# TensoSensor_EXTRA.net
KiCad netlist of a schematic drawn in Altium Designer
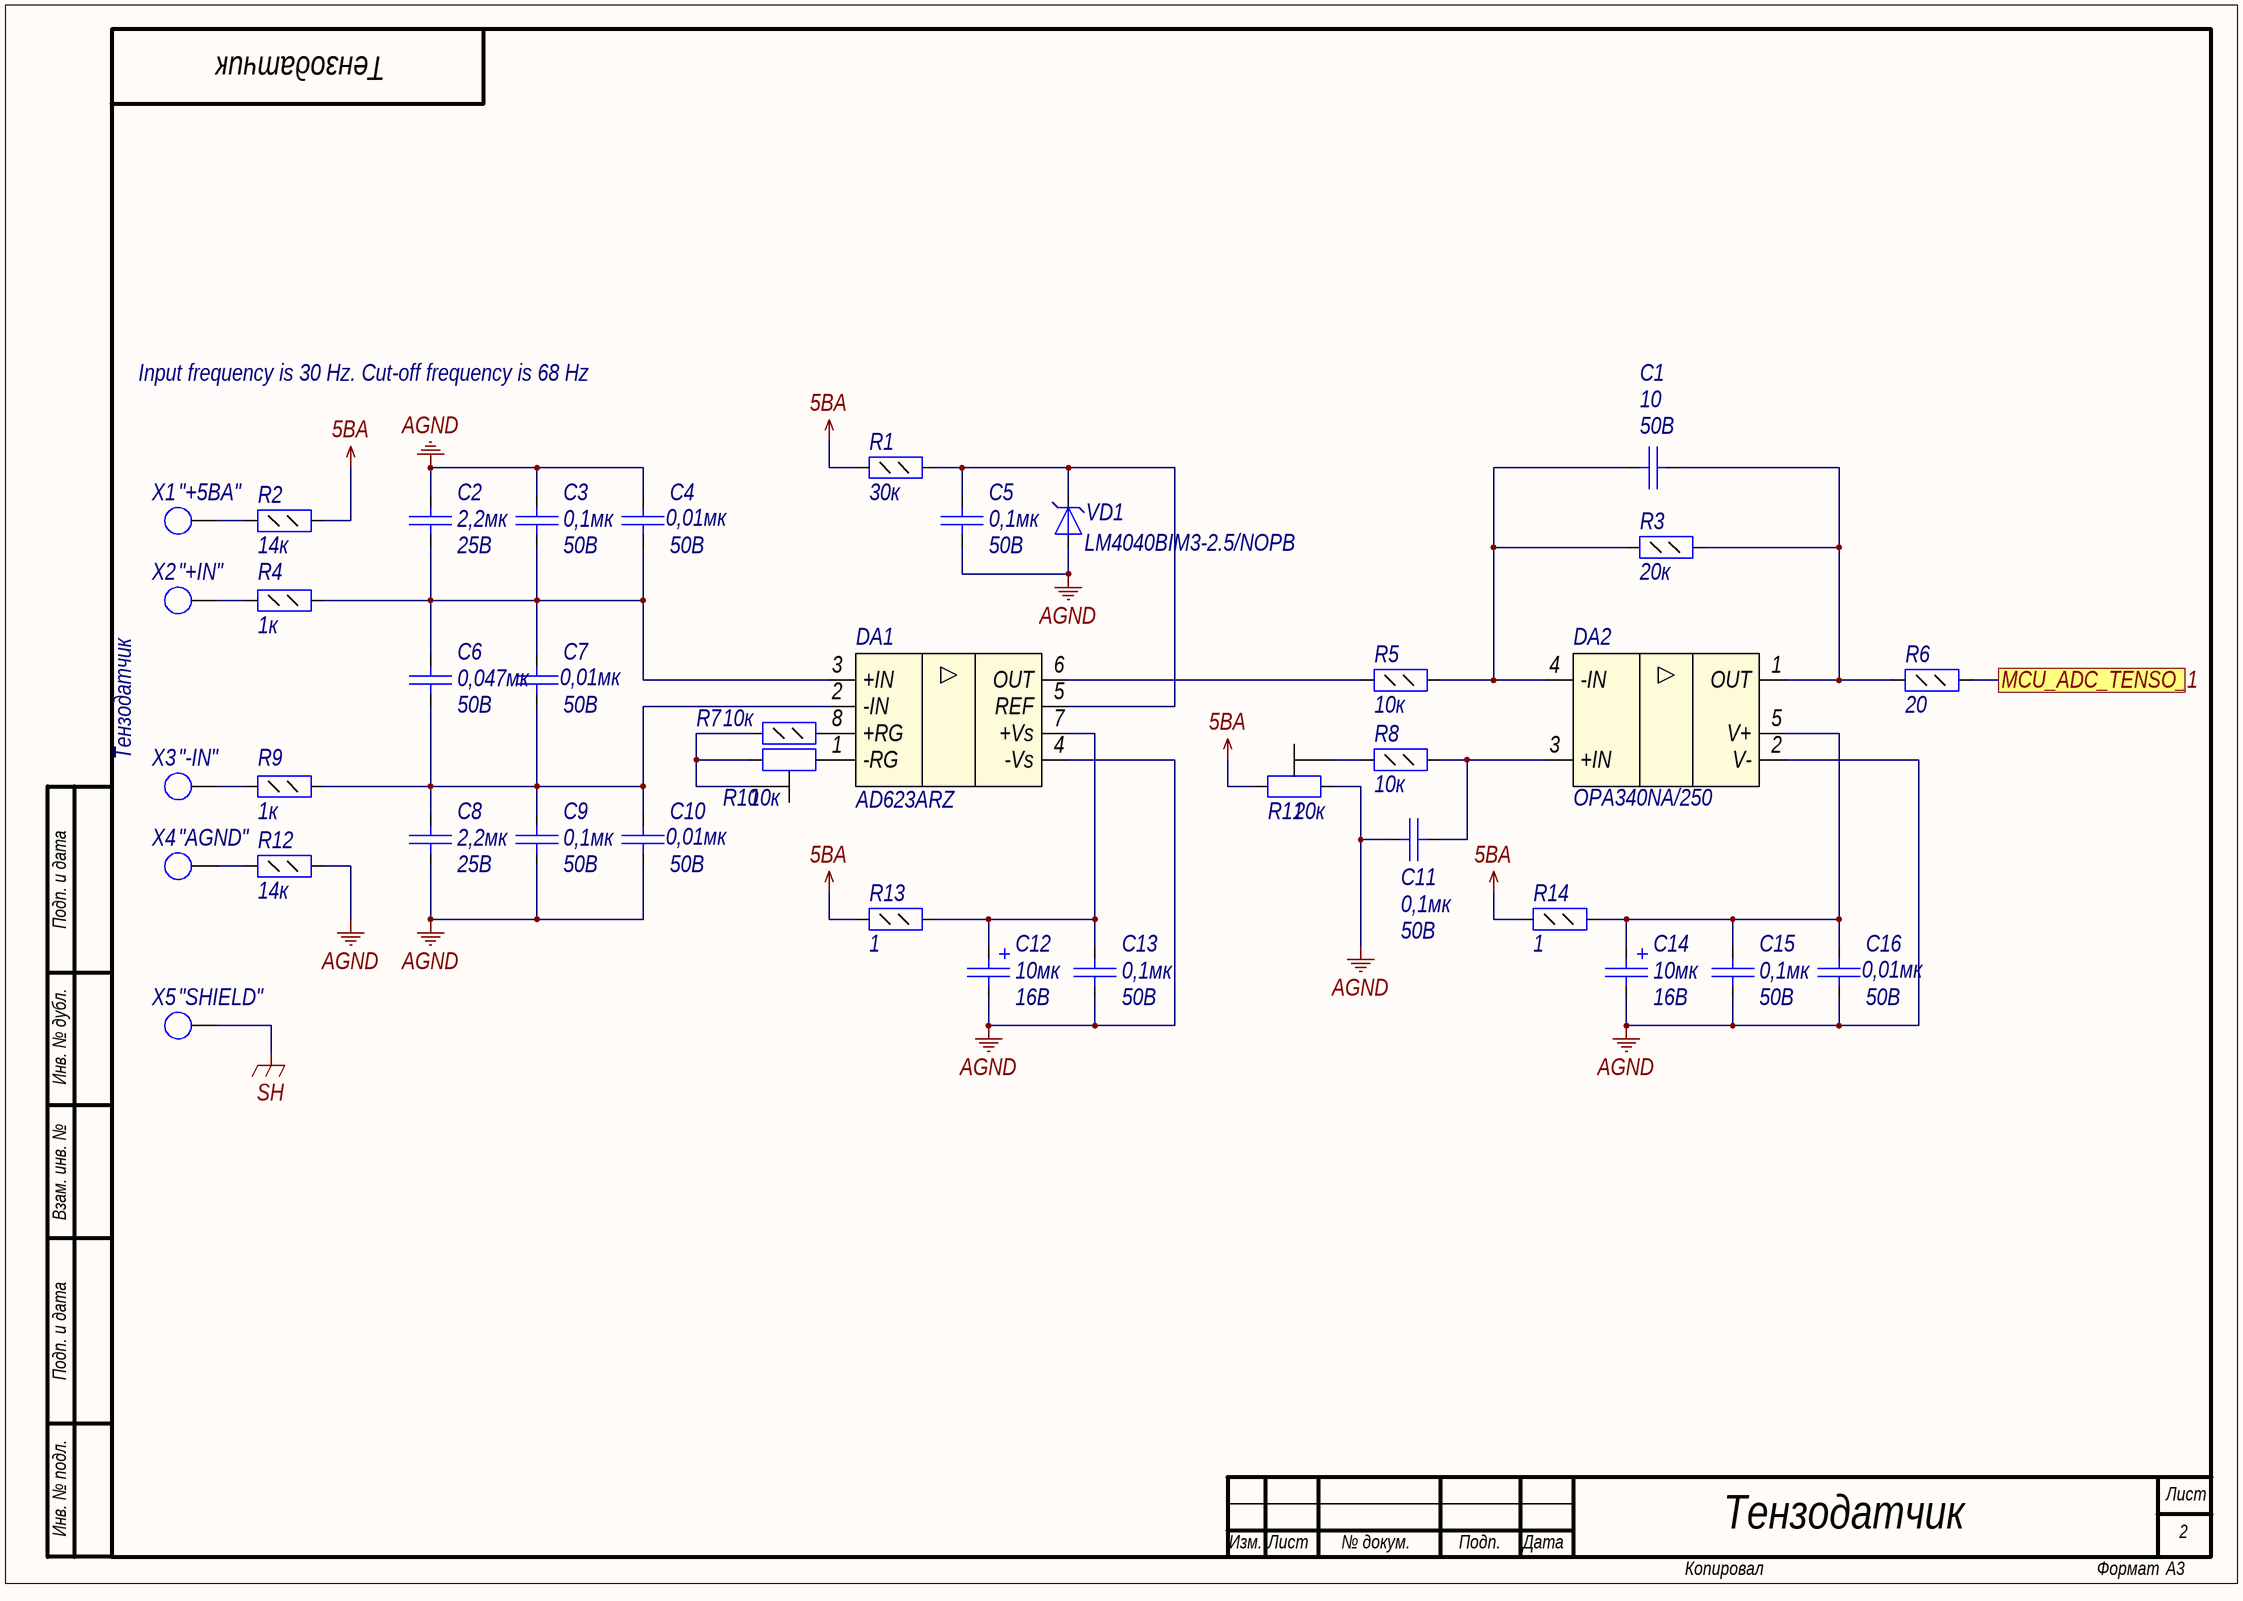
[diagram p0: TensoSensor_EXTRA.SchDoc]

(export (version "E")
  (design (tool "Eeschema 10.0.6"))
  (components
    (comp (ref "C1")
      (value "10")
      (footprint "C0603")
      (description "Конденсатор")
      (fields (field (name "VOLTAGE") "50B") (field (name "PART NUMBER") "GRM1885C1H100J"))
      (libsource (lib "MOP44") (part "Capacitor"))
    )
    (comp (ref "C2")
      (value "2,2мк")
      (footprint "C0805")
      (description "Конденсатор")
      (fields (field (name "VOLTAGE") "25B") (field (name "PART NUMBER") "GRM21BR71E225K"))
      (libsource (lib "MOP44") (part "Capacitor"))
    )
    (comp (ref "C3")
      (value "0,1мк")
      (footprint "C0805")
      (description "Конденсатор")
      (fields (field (name "VOLTAGE") "50B") (field (name "PART NUMBER") "GRM21BR71H104K**"))
      (libsource (lib "MOP44") (part "Capacitor"))
    )
    (comp (ref "C4")
      (value "0,01мк")
      (footprint "C0805")
      (description "Конденсатор")
      (fields (field (name "VOLTAGE") "50B") (field (name "PART NUMBER") "GRM216R71H103K"))
      (libsource (lib "MOP44") (part "Capacitor"))
    )
    (comp (ref "C5")
      (value "0,1мк")
      (footprint "C0805")
      (description "Конденсатор")
      (fields (field (name "VOLTAGE") "50B") (field (name "PART NUMBER") "GRM21BR71H104K**"))
      (libsource (lib "MOP44") (part "Capacitor"))
    )
    (comp (ref "C6")
      (value "0,047мк")
      (footprint "C0805")
      (description "Конденсатор")
      (fields (field (name "VOLTAGE") "50B") (field (name "PART NUMBER") "GRM21BR71H473K"))
      (libsource (lib "MOP44") (part "Capacitor"))
    )
    (comp (ref "C7")
      (value "0,01мк")
      (footprint "C0805")
      (description "Конденсатор")
      (fields (field (name "VOLTAGE") "50B") (field (name "PART NUMBER") "GRM216R71H103K"))
      (libsource (lib "MOP44") (part "Capacitor"))
    )
    (comp (ref "C8")
      (value "2,2мк")
      (footprint "C0805")
      (description "Конденсатор")
      (fields (field (name "VOLTAGE") "25B") (field (name "PART NUMBER") "GRM21BR71E225K"))
      (libsource (lib "MOP44") (part "Capacitor"))
    )
    (comp (ref "C9")
      (value "0,1мк")
      (footprint "C0805")
      (description "Конденсатор")
      (fields (field (name "VOLTAGE") "50B") (field (name "PART NUMBER") "GRM21BR71H104K**"))
      (libsource (lib "MOP44") (part "Capacitor"))
    )
    (comp (ref "C10")
      (value "0,01мк")
      (footprint "C0805")
      (description "Конденсатор")
      (fields (field (name "VOLTAGE") "50B") (field (name "PART NUMBER") "GRM216R71H103K"))
      (libsource (lib "MOP44") (part "Capacitor"))
    )
    (comp (ref "C11")
      (value "0,1мк")
      (footprint "C0805")
      (description "Конденсатор")
      (fields (field (name "VOLTAGE") "50B") (field (name "PART NUMBER") "GRM21BR71H104K**"))
      (libsource (lib "MOP44") (part "Capacitor"))
    )
    (comp (ref "C12")
      (value "10мк")
      (footprint "TANTAL CASE A")
      (description "Конденсатор полярный")
      (fields
        (field (name "VOLTAGE") "16В")
        (field (name "PART NUMBER") "293D106X9016A2TE3")
        (field (name "Comment") "Capacitor_pol")
      )
      (libsource (lib "MOP44") (part "Capacitor_pol"))
    )
    (comp (ref "C13")
      (value "0,1мк")
      (footprint "C0805")
      (description "Конденсатор")
      (fields (field (name "VOLTAGE") "50B") (field (name "PART NUMBER") "GRM21BR71H104K**"))
      (libsource (lib "MOP44") (part "Capacitor"))
    )
    (comp (ref "C14")
      (value "10мк")
      (footprint "TANTAL CASE A")
      (description "Конденсатор полярный")
      (fields
        (field (name "VOLTAGE") "16В")
        (field (name "PART NUMBER") "293D106X9016A2TE3")
        (field (name "Comment") "Capacitor_pol")
      )
      (libsource (lib "MOP44") (part "Capacitor_pol"))
    )
    (comp (ref "C15")
      (value "0,1мк")
      (footprint "C0805")
      (description "Конденсатор")
      (fields (field (name "VOLTAGE") "50B") (field (name "PART NUMBER") "GRM21BR71H104K**"))
      (libsource (lib "MOP44") (part "Capacitor"))
    )
    (comp (ref "C16")
      (value "0,01мк")
      (footprint "C0805")
      (description "Конденсатор")
      (fields (field (name "VOLTAGE") "50B") (field (name "PART NUMBER") "GRM216R71H103K"))
      (libsource (lib "MOP44") (part "Capacitor"))
    )
    (comp (ref "DA1")
      (value "AD623ARZ")
      (footprint "SO8")
      (description "Low Cost Low Power  Instrumentation Amplifier")
      (libsource (lib "MOP44") (part "AD623ARZ"))
    )
    (comp (ref "DA2")
      (value "OPA340")
      (footprint "SOT23-5")
      (description "Operational Amplifiers\r\nMicroAmplifier")
      (fields (field (name "PART NUMBER") "OPA340NA/250"))
      (libsource (lib "MOP44") (part "OPA340"))
    )
    (comp (ref "R1")
      (value "30к")
      (footprint "R0805")
      (description "Резистор")
      (fields (field (name "PART NUMBER") "RC0805FR-0730KL") (field (name "POWER") "0,125Вт"))
      (libsource (lib "MOP44") (part "Resistor_0,125Вт"))
    )
    (comp (ref "R2")
      (value "14к")
      (footprint "R0805")
      (description "Резистор")
      (fields (field (name "PART NUMBER") "RC0805FR-0714KL") (field (name "POWER") "0,125Вт"))
      (libsource (lib "MOP44") (part "Resistor_0,125Вт"))
    )
    (comp (ref "R3")
      (value "20к")
      (footprint "R0805")
      (description "Резистор")
      (fields (field (name "PART NUMBER") "RC0805FR-0720KL") (field (name "POWER") "0,125Вт"))
      (libsource (lib "MOP44") (part "Resistor_0,125Вт"))
    )
    (comp (ref "R4")
      (value "1к")
      (footprint "R0805")
      (description "Резистор")
      (fields (field (name "PART NUMBER") "RC0805FR-071KL") (field (name "POWER") "0,125Вт"))
      (libsource (lib "MOP44") (part "Resistor_0,125Вт"))
    )
    (comp (ref "R5")
      (value "10к")
      (footprint "R0805")
      (description "Резистор")
      (fields (field (name "PART NUMBER") "RC0805FR-0710KL") (field (name "POWER") "0,125Вт"))
      (libsource (lib "MOP44") (part "Resistor_0,125Вт"))
    )
    (comp (ref "R6")
      (value "20")
      (footprint "R0805")
      (description "Резистор")
      (fields (field (name "PART NUMBER") "RC0805FR-0720RL") (field (name "POWER") "0,125Вт"))
      (libsource (lib "MOP44") (part "Resistor_0,125Вт"))
    )
    (comp (ref "R7")
      (value "10к")
      (footprint "R0805")
      (description "Резистор")
      (fields (field (name "PART NUMBER") "RC0805FR-0710KL") (field (name "POWER") "0,125Вт"))
      (libsource (lib "MOP44") (part "Resistor_0,125Вт"))
    )
    (comp (ref "R8")
      (value "10к")
      (footprint "R0805")
      (description "Резистор")
      (fields (field (name "PART NUMBER") "RC0805FR-0710KL") (field (name "POWER") "0,125Вт"))
      (libsource (lib "MOP44") (part "Resistor_0,125Вт"))
    )
    (comp (ref "R9")
      (value "1к")
      (footprint "R0805")
      (description "Резистор")
      (fields (field (name "PART NUMBER") "RC0805FR-071KL") (field (name "POWER") "0,125Вт"))
      (libsource (lib "MOP44") (part "Resistor_0,125Вт"))
    )
    (comp (ref "R10")
      (value "10к")
      (footprint "3224W")
      (description "Potentiometer")
      (fields (field (name "PART NUMBER") "3224W-1-103E") (field (name "POWER") "0,25Вт"))
      (libsource (lib "MOP44") (part "Potentiometer"))
    )
    (comp (ref "R11")
      (value "20к")
      (footprint "3224W")
      (description "Potentiometer")
      (fields (field (name "PART NUMBER") "3224W-1-203E") (field (name "POWER") "0,25Вт"))
      (libsource (lib "") (part "Potentiometer_1"))
    )
    (comp (ref "R12")
      (value "14к")
      (footprint "R0805")
      (description "Резистор")
      (fields (field (name "PART NUMBER") "RC0805FR-0714KL") (field (name "POWER") "0,125Вт"))
      (libsource (lib "MOP44") (part "Resistor_0,125Вт"))
    )
    (comp (ref "R13")
      (value "1")
      (footprint "R0805")
      (description "Резистор")
      (fields (field (name "PART NUMBER") "RC0805FR-071RL") (field (name "POWER") "0,125Вт"))
      (libsource (lib "MOP44") (part "Resistor_0,125Вт"))
    )
    (comp (ref "R14")
      (value "1")
      (footprint "R0805")
      (description "Резистор")
      (fields (field (name "PART NUMBER") "RC0805FR-071RL") (field (name "POWER") "0,125Вт"))
      (libsource (lib "MOP44") (part "Resistor_0,125Вт"))
    )
    (comp (ref "VD1")
      (value "LM4040BIM3-2.5/NOPB")
      (footprint "SOT23-3")
      (description "Прецезионный источник опорного напряжения")
      (libsource (lib "MOP44") (part "LM4040BIM3-2.5/NOPB"))
    )
    (comp (ref "X1") (value "SoldPoint") (footprint "1HOLE") (libsource (lib "MOP44") (part "SoldPoint")))
    (comp (ref "X2") (value "SoldPoint") (footprint "1HOLE") (libsource (lib "MOP44") (part "SoldPoint")))
    (comp (ref "X3") (value "SoldPoint") (footprint "1HOLE") (libsource (lib "MOP44") (part "SoldPoint")))
    (comp (ref "X4") (value "SoldPoint") (footprint "1HOLE") (libsource (lib "MOP44") (part "SoldPoint")))
    (comp (ref "X5") (value "SoldPoint") (footprint "1HOLE") (libsource (lib "MOP44") (part "SoldPoint")))
  )
  (nets
    (net (code "1") (name "/MCU_ADC_TENSO_1") (class "Default")
      (node (ref "R6") (pin "2") (pinfunction "2_2") (pintype "passive"))
    )
    (net (code "2") (name "5BA") (class "Default")
      (node (ref "R1") (pin "1") (pinfunction "1_1") (pintype "passive"))
      (node (ref "R11") (pin "1") (pinfunction "1_1") (pintype "passive"))
      (node (ref "R13") (pin "1") (pinfunction "1_1") (pintype "passive"))
      (node (ref "R14") (pin "1") (pinfunction "1_1") (pintype "passive"))
      (node (ref "R2") (pin "2") (pinfunction "2_2") (pintype "passive"))
    )
    (net (code "3") (name "AGND") (class "Default")
      (node (ref "C10") (pin "1") (pinfunction "1_1") (pintype "passive"))
      (node (ref "C11") (pin "2") (pinfunction "2_2") (pintype "passive"))
      (node (ref "C12") (pin "2") (pinfunction "2_2") (pintype "passive"))
      (node (ref "C13") (pin "1") (pinfunction "1_1") (pintype "passive"))
      (node (ref "C14") (pin "2") (pinfunction "2_2") (pintype "passive"))
      (node (ref "C15") (pin "1") (pinfunction "1_1") (pintype "passive"))
      (node (ref "C16") (pin "1") (pinfunction "1_1") (pintype "passive"))
      (node (ref "C2") (pin "2") (pinfunction "2_2") (pintype "passive"))
      (node (ref "C3") (pin "2") (pinfunction "2_2") (pintype "passive"))
      (node (ref "C4") (pin "2") (pinfunction "2_2") (pintype "passive"))
      (node (ref "C5") (pin "1") (pinfunction "1_1") (pintype "passive"))
      (node (ref "C8") (pin "1") (pinfunction "1_1") (pintype "passive"))
      (node (ref "C9") (pin "1") (pinfunction "1_1") (pintype "passive"))
      (node (ref "DA1") (pin "4") (pinfunction "-Vs_4") (pintype "passive"))
      (node (ref "DA2") (pin "2") (pinfunction "V-_2") (pintype "passive"))
      (node (ref "R11") (pin "3") (pinfunction "3_3") (pintype "passive"))
      (node (ref "R12") (pin "2") (pinfunction "2_2") (pintype "passive"))
      (node (ref "VD1") (pin "2") (pinfunction "A_2") (pintype "passive"))
    )
    (net (code "4") (name "Net-(DA1-+IN)") (class "Default")
      (node (ref "C2") (pin "1") (pinfunction "1_1") (pintype "passive"))
      (node (ref "C3") (pin "1") (pinfunction "1_1") (pintype "passive"))
      (node (ref "C4") (pin "1") (pinfunction "1_1") (pintype "passive"))
      (node (ref "C6") (pin "2") (pinfunction "2_2") (pintype "passive"))
      (node (ref "C7") (pin "2") (pinfunction "2_2") (pintype "passive"))
      (node (ref "DA1") (pin "3") (pinfunction "+IN_3") (pintype "passive"))
      (node (ref "R4") (pin "2") (pinfunction "2_2") (pintype "passive"))
    )
    (net (code "5") (name "Net-(DA1-+RG)") (class "Default")
      (node (ref "DA1") (pin "8") (pinfunction "+RG_8") (pintype "passive"))
      (node (ref "R7") (pin "2") (pinfunction "2_2") (pintype "passive"))
    )
    (net (code "6") (name "Net-(DA1-+Vs)") (class "Default")
      (node (ref "C12") (pin "1") (pinfunction "1_1") (pintype "passive"))
      (node (ref "C13") (pin "2") (pinfunction "2_2") (pintype "passive"))
      (node (ref "DA1") (pin "7") (pinfunction "+Vs_7") (pintype "passive"))
      (node (ref "R13") (pin "2") (pinfunction "2_2") (pintype "passive"))
    )
    (net (code "7") (name "Net-(DA1--IN)") (class "Default")
      (node (ref "C10") (pin "2") (pinfunction "2_2") (pintype "passive"))
      (node (ref "C6") (pin "1") (pinfunction "1_1") (pintype "passive"))
      (node (ref "C7") (pin "1") (pinfunction "1_1") (pintype "passive"))
      (node (ref "C8") (pin "2") (pinfunction "2_2") (pintype "passive"))
      (node (ref "C9") (pin "2") (pinfunction "2_2") (pintype "passive"))
      (node (ref "DA1") (pin "2") (pinfunction "-IN_2") (pintype "passive"))
      (node (ref "R9") (pin "2") (pinfunction "2_2") (pintype "passive"))
    )
    (net (code "8") (name "Net-(DA1--RG)") (class "Default")
      (node (ref "DA1") (pin "1") (pinfunction "-RG_1") (pintype "passive"))
      (node (ref "R10") (pin "1") (pinfunction "1_1") (pintype "passive"))
    )
    (net (code "9") (name "Net-(DA1-OUT)") (class "Default")
      (node (ref "DA1") (pin "6") (pinfunction "OUT_6") (pintype "passive"))
      (node (ref "R5") (pin "1") (pinfunction "1_1") (pintype "passive"))
    )
    (net (code "10") (name "Net-(DA1-REF)") (class "Default")
      (node (ref "C5") (pin "2") (pinfunction "2_2") (pintype "passive"))
      (node (ref "DA1") (pin "5") (pinfunction "REF_5") (pintype "passive"))
      (node (ref "R1") (pin "2") (pinfunction "2_2") (pintype "passive"))
      (node (ref "VD1") (pin "1") (pinfunction "K_1") (pintype "passive"))
    )
    (net (code "11") (name "Net-(DA2-+IN)") (class "Default")
      (node (ref "C11") (pin "1") (pinfunction "1_1") (pintype "passive"))
      (node (ref "DA2") (pin "3") (pinfunction "+IN_3") (pintype "passive"))
      (node (ref "R8") (pin "2") (pinfunction "2_2") (pintype "passive"))
    )
    (net (code "12") (name "Net-(DA2--IN)") (class "Default")
      (node (ref "C1") (pin "1") (pinfunction "1_1") (pintype "passive"))
      (node (ref "DA2") (pin "4") (pinfunction "-IN_4") (pintype "passive"))
      (node (ref "R3") (pin "1") (pinfunction "1_1") (pintype "passive"))
      (node (ref "R5") (pin "2") (pinfunction "2_2") (pintype "passive"))
    )
    (net (code "13") (name "Net-(DA2-OUT)") (class "Default")
      (node (ref "C1") (pin "2") (pinfunction "2_2") (pintype "passive"))
      (node (ref "DA2") (pin "1") (pinfunction "OUT_1") (pintype "passive"))
      (node (ref "R3") (pin "2") (pinfunction "2_2") (pintype "passive"))
      (node (ref "R6") (pin "1") (pinfunction "1_1") (pintype "passive"))
    )
    (net (code "14") (name "Net-(DA2-V+)") (class "Default")
      (node (ref "C14") (pin "1") (pinfunction "1_1") (pintype "passive"))
      (node (ref "C15") (pin "2") (pinfunction "2_2") (pintype "passive"))
      (node (ref "C16") (pin "2") (pinfunction "2_2") (pintype "passive"))
      (node (ref "DA2") (pin "5") (pinfunction "V+_5") (pintype "passive"))
      (node (ref "R14") (pin "2") (pinfunction "2_2") (pintype "passive"))
    )
    (net (code "15") (name "Net-(R2-Pad1)") (class "Default")
      (node (ref "R2") (pin "1") (pinfunction "1_1") (pintype "passive"))
      (node (ref "X1") (pin "1") (pinfunction "1_1") (pintype "passive"))
    )
    (net (code "16") (name "Net-(R4-Pad1)") (class "Default")
      (node (ref "R4") (pin "1") (pinfunction "1_1") (pintype "passive"))
      (node (ref "X2") (pin "1") (pinfunction "1_1") (pintype "passive"))
    )
    (net (code "17") (name "Net-(R9-Pad1)") (class "Default")
      (node (ref "R9") (pin "1") (pinfunction "1_1") (pintype "passive"))
      (node (ref "X3") (pin "1") (pinfunction "1_1") (pintype "passive"))
    )
    (net (code "18") (name "Net-(R10-Pad2)") (class "Default")
      (node (ref "R10") (pin "2") (pinfunction "2_2") (pintype "passive"))
      (node (ref "R10") (pin "3") (pinfunction "3_3") (pintype "passive"))
      (node (ref "R7") (pin "1") (pinfunction "1_1") (pintype "passive"))
    )
    (net (code "19") (name "Net-(R11-Pad2)") (class "Default")
      (node (ref "R11") (pin "2") (pinfunction "2_2") (pintype "passive"))
      (node (ref "R8") (pin "1") (pinfunction "1_1") (pintype "passive"))
    )
    (net (code "20") (name "Net-(R12-Pad1)") (class "Default")
      (node (ref "R12") (pin "1") (pinfunction "1_1") (pintype "passive"))
      (node (ref "X4") (pin "1") (pinfunction "1_1") (pintype "passive"))
    )
    (net (code "21") (name "SH") (class "Default")
      (node (ref "X5") (pin "1") (pinfunction "1_1") (pintype "passive"))
    )
  )
)
